# sdram.net
KiCad netlist of a schematic drawn in Altium Designer
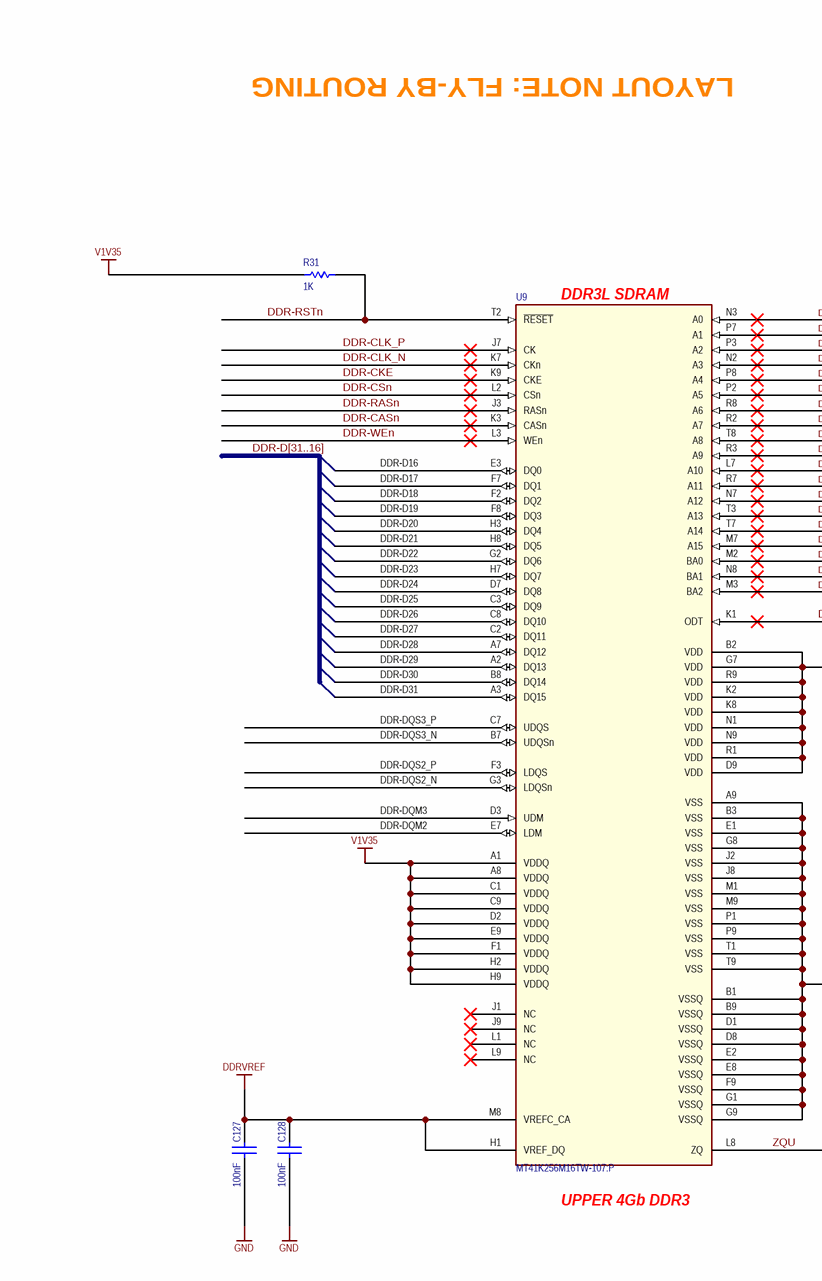
[diagram p0: sdram.SchDoc, top left]
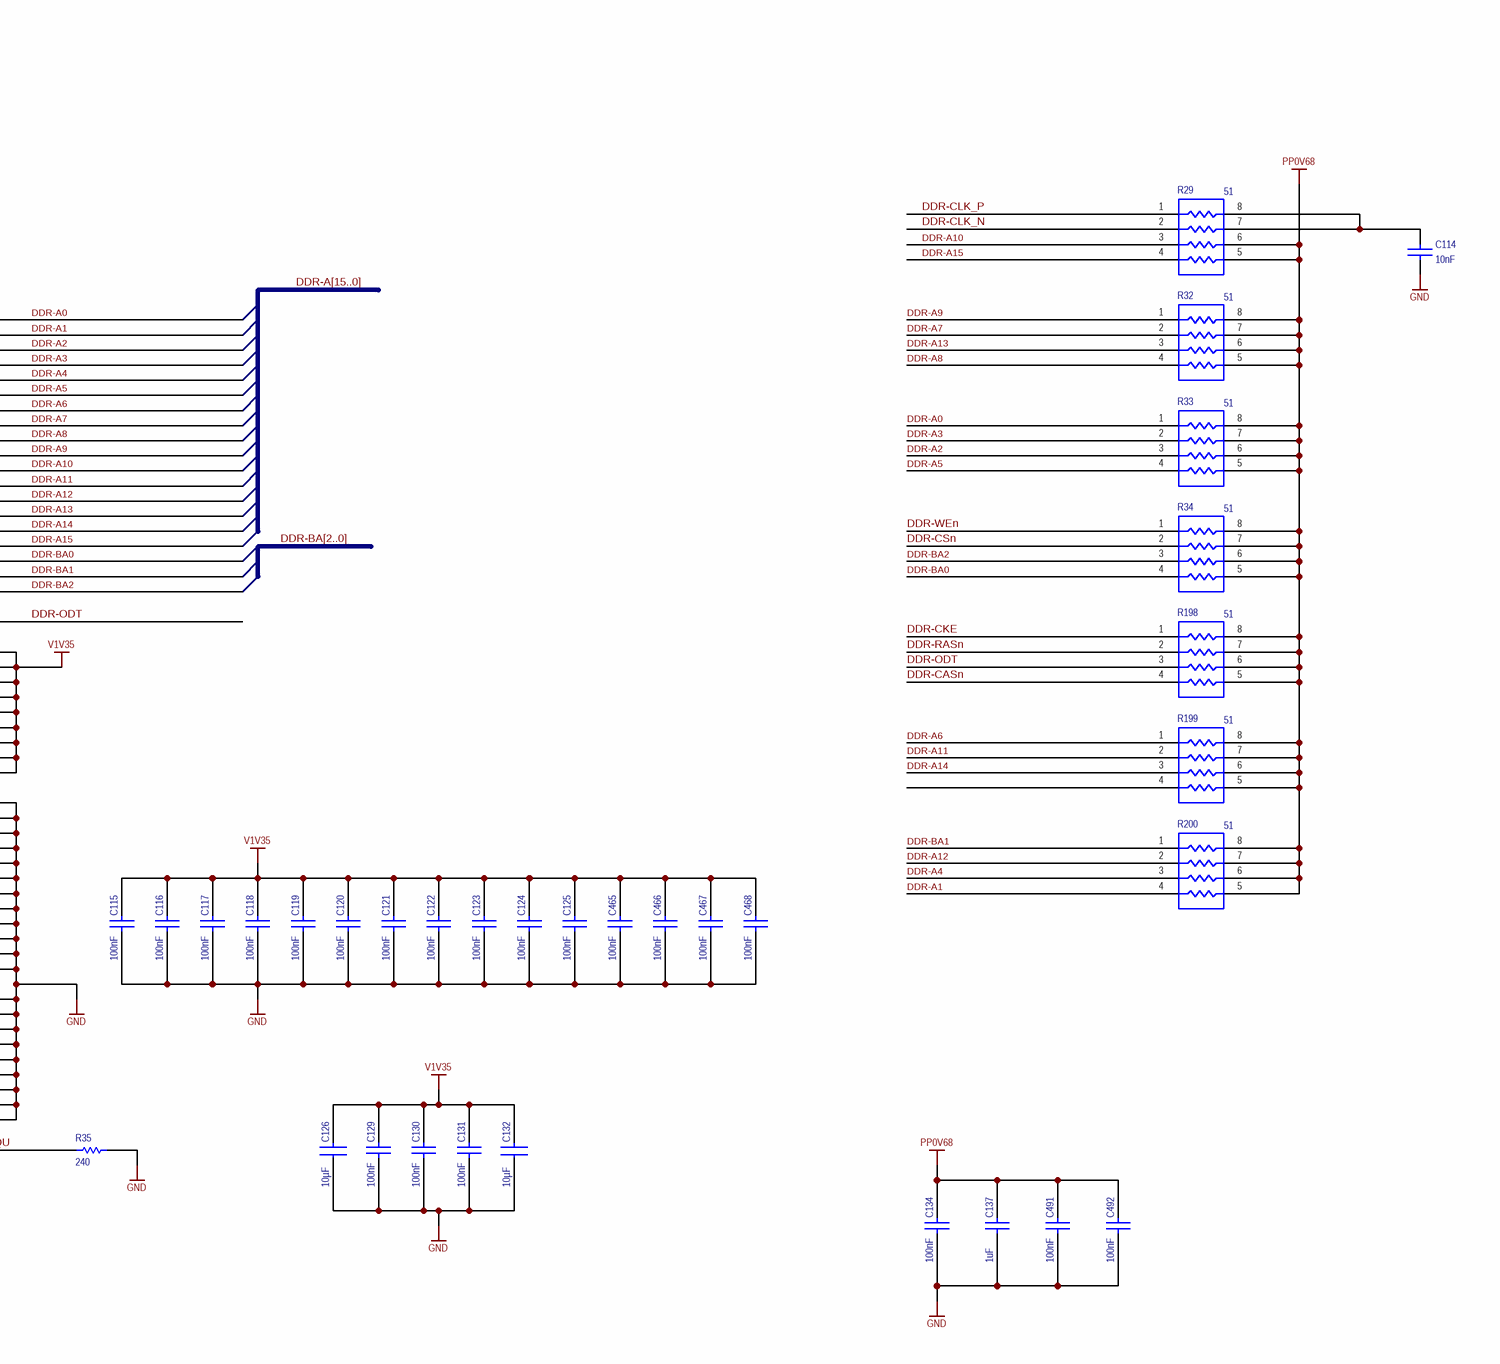
[diagram p1: sdram.SchDoc, top right]
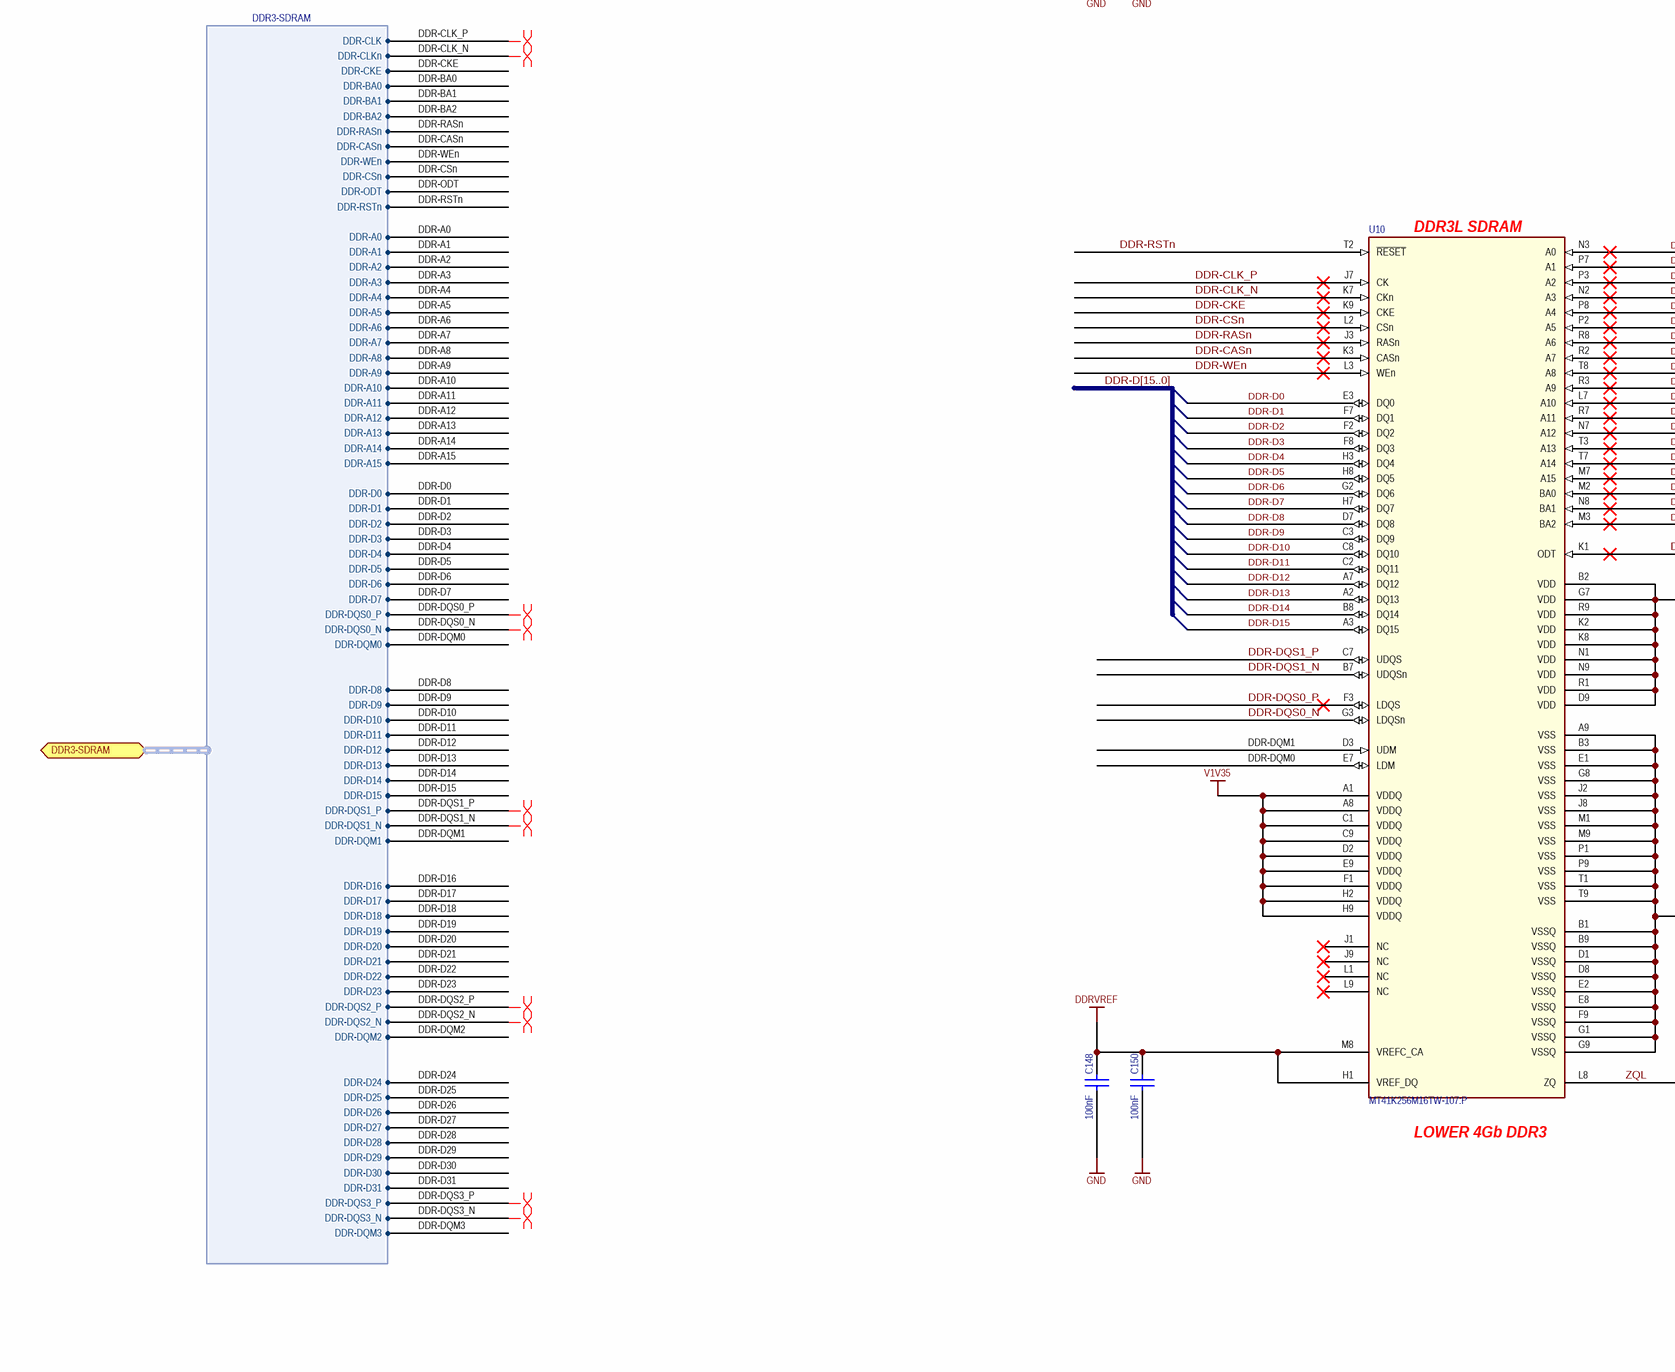
[diagram p2: sdram.SchDoc, bottom left]
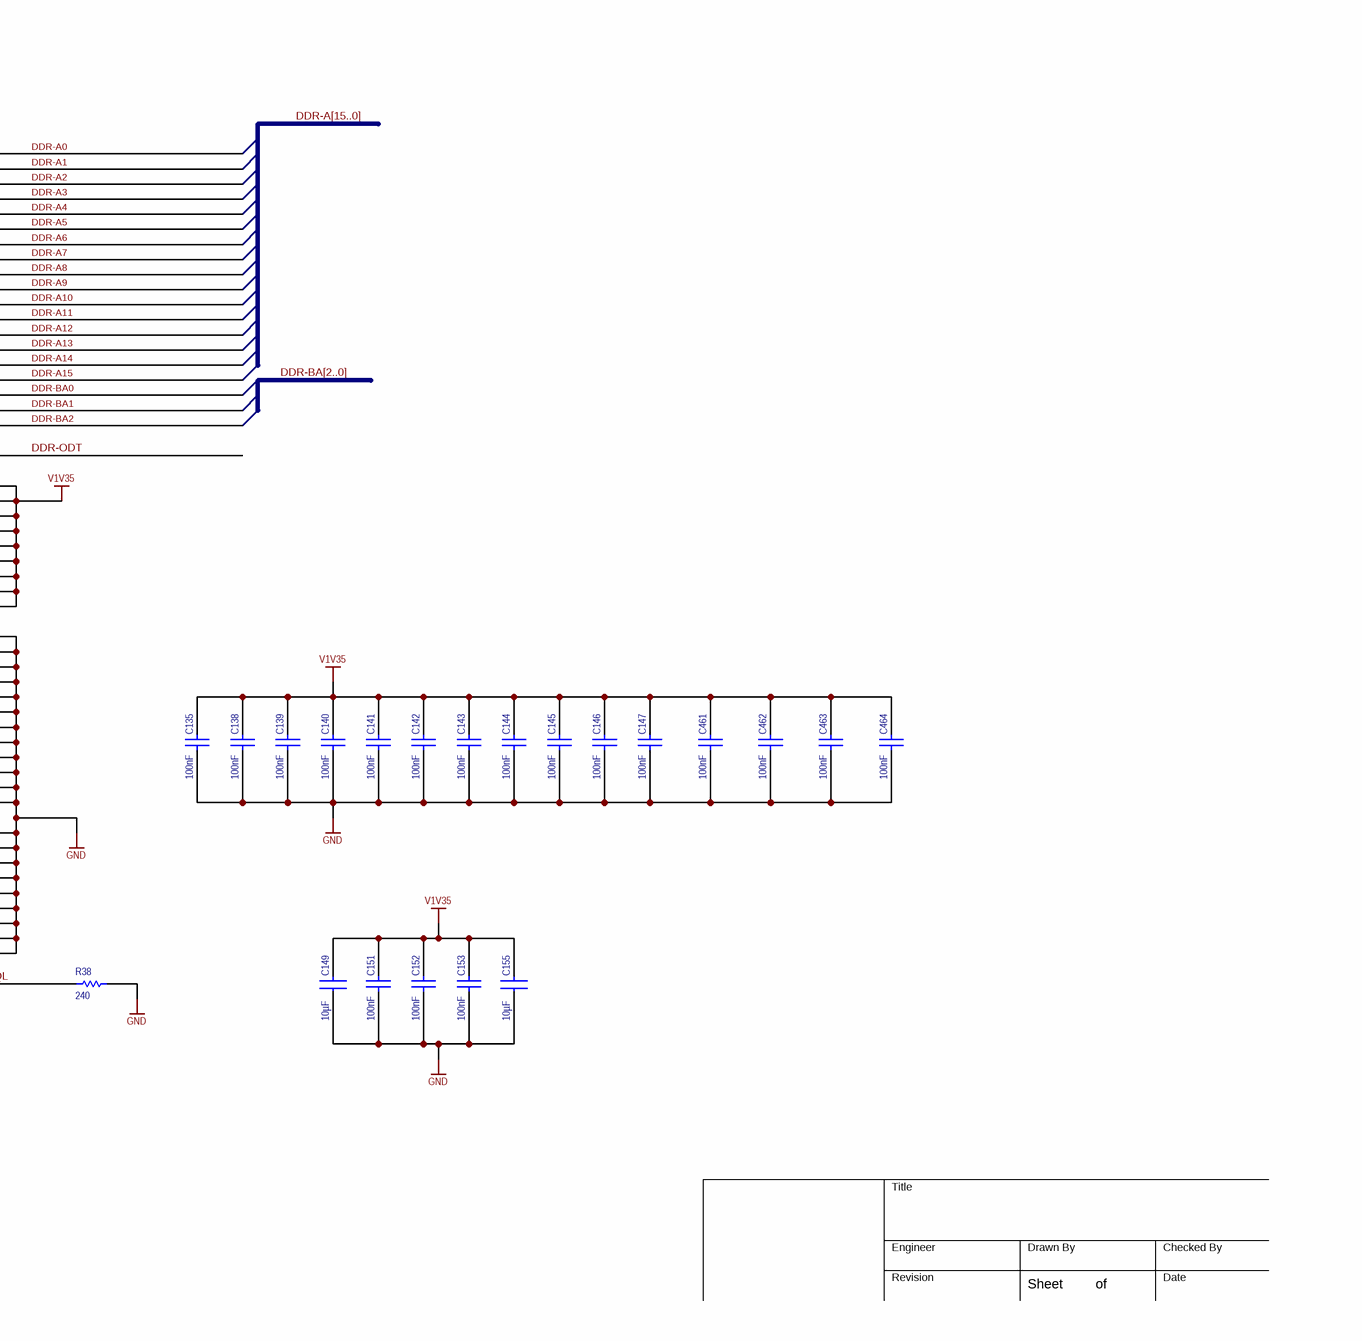
[diagram p3: sdram.SchDoc, bottom right]

(export (version "E")
  (design (tool "Eeschema 10.0.6"))
  (components
    (comp (ref "C114")
      (value "10nF")
      (footprint "generic:0402")
      (description "Ceramic Capacitor 10nF ±10% 25V X7R 0402")
      (fields (field (name "VOLTAGE") "25V") (field (name "MANUFACTURER") "Murata"))
      (libsource (lib "Graviton") (part "CAP 0402"))
    )
    (comp (ref "C115")
      (value "100nF")
      (footprint "generic:CAPC1005X56N")
      (description "Ceramic Capacitor 100nF ±10% 16V X7R 0402")
      (fields (field (name "MANUFACTURER") "Murata") (field (name "TOLERANCE") "±10%"))
      (libsource (lib "murata") (part "GRM155R71A104KA01J"))
    )
    (comp (ref "C116")
      (value "100nF")
      (footprint "generic:CAPC1005X56N")
      (description "Ceramic Capacitor 100nF ±10% 16V X7R 0402")
      (fields (field (name "MANUFACTURER") "Murata") (field (name "TOLERANCE") "±10%"))
      (libsource (lib "murata") (part "GRM155R71A104KA01J"))
    )
    (comp (ref "C117")
      (value "100nF")
      (footprint "generic:CAPC1005X56N")
      (description "Ceramic Capacitor 100nF ±10% 16V X7R 0402")
      (fields (field (name "MANUFACTURER") "Murata") (field (name "TOLERANCE") "±10%"))
      (libsource (lib "murata") (part "GRM155R71A104KA01J"))
    )
    (comp (ref "C118")
      (value "100nF")
      (footprint "generic:CAPC1005X56N")
      (description "Ceramic Capacitor 100nF ±10% 16V X7R 0402")
      (fields (field (name "MANUFACTURER") "Murata") (field (name "TOLERANCE") "±10%"))
      (libsource (lib "murata") (part "GRM155R71A104KA01J"))
    )
    (comp (ref "C119")
      (value "100nF")
      (footprint "generic:CAPC1005X56N")
      (description "Ceramic Capacitor 100nF ±10% 16V X7R 0402")
      (fields (field (name "MANUFACTURER") "Murata") (field (name "TOLERANCE") "±10%"))
      (libsource (lib "murata") (part "GRM155R71A104KA01J"))
    )
    (comp (ref "C120")
      (value "100nF")
      (footprint "generic:CAPC1005X56N")
      (description "Ceramic Capacitor 100nF ±10% 16V X7R 0402")
      (fields (field (name "MANUFACTURER") "Murata") (field (name "TOLERANCE") "±10%"))
      (libsource (lib "murata") (part "GRM155R71A104KA01J"))
    )
    (comp (ref "C121")
      (value "100nF")
      (footprint "generic:CAPC1005X56N")
      (description "Ceramic Capacitor 100nF ±10% 16V X7R 0402")
      (fields (field (name "MANUFACTURER") "Murata") (field (name "TOLERANCE") "±10%"))
      (libsource (lib "murata") (part "GRM155R71A104KA01J"))
    )
    (comp (ref "C122")
      (value "100nF")
      (footprint "generic:CAPC1005X56N")
      (description "Ceramic Capacitor 100nF ±10% 16V X7R 0402")
      (fields (field (name "MANUFACTURER") "Murata") (field (name "TOLERANCE") "±10%"))
      (libsource (lib "murata") (part "GRM155R71A104KA01J"))
    )
    (comp (ref "C123")
      (value "100nF")
      (footprint "generic:CAPC1005X56N")
      (description "Ceramic Capacitor 100nF ±10% 16V X7R 0402")
      (fields (field (name "MANUFACTURER") "Murata") (field (name "TOLERANCE") "±10%"))
      (libsource (lib "murata") (part "GRM155R71A104KA01J"))
    )
    (comp (ref "C124")
      (value "100nF")
      (footprint "generic:CAPC1005X56N")
      (description "Ceramic Capacitor 100nF ±10% 16V X7R 0402")
      (fields (field (name "MANUFACTURER") "Murata") (field (name "TOLERANCE") "±10%"))
      (libsource (lib "murata") (part "GRM155R71A104KA01J"))
    )
    (comp (ref "C125")
      (value "100nF")
      (footprint "generic:CAPC1005X56N")
      (description "Ceramic Capacitor 100nF ±10% 16V X7R 0402")
      (fields (field (name "MANUFACTURER") "Murata") (field (name "TOLERANCE") "±10%"))
      (libsource (lib "murata") (part "GRM155R71A104KA01J"))
    )
    (comp (ref "C126")
      (value "10µF")
      (footprint "0603")
      (description "Ceramic Capacitor 10uF ±20% 25V X5R 0603")
      (fields (field (name "MANUFACTURER") "Samsung") (field (name "TOLERANCE") "±20%"))
      (libsource (lib "BEAGLEBONEBLACK_REV A5B") (part "CAP_4.7uF_X5R_6.3V_10%_0603"))
    )
    (comp (ref "C127")
      (value "100nF")
      (footprint "generic:CAPC1005X56N")
      (description "Ceramic Capacitor 100nF ±10% 16V X7R 0402")
      (fields (field (name "MANUFACTURER") "Murata") (field (name "TOLERANCE") "±10%"))
      (libsource (lib "murata") (part "GRM155R71A104KA01J"))
    )
    (comp (ref "C128")
      (value "100nF")
      (footprint "generic:CAPC1005X56N")
      (description "Ceramic Capacitor 100nF ±10% 16V X7R 0402")
      (fields (field (name "MANUFACTURER") "Murata") (field (name "TOLERANCE") "±10%"))
      (libsource (lib "murata") (part "GRM155R71A104KA01J"))
    )
    (comp (ref "C129")
      (value "100nF")
      (footprint "generic:CAPC1005X56N")
      (description "Ceramic Capacitor 100nF ±10% 16V X7R 0402")
      (fields (field (name "MANUFACTURER") "Murata") (field (name "TOLERANCE") "±10%"))
      (libsource (lib "murata") (part "GRM155R71A104KA01J"))
    )
    (comp (ref "C130")
      (value "100nF")
      (footprint "generic:CAPC1005X56N")
      (description "Ceramic Capacitor 100nF ±10% 16V X7R 0402")
      (fields (field (name "MANUFACTURER") "Murata") (field (name "TOLERANCE") "±10%"))
      (libsource (lib "murata") (part "GRM155R71A104KA01J"))
    )
    (comp (ref "C131")
      (value "100nF")
      (footprint "generic:CAPC1005X56N")
      (description "Ceramic Capacitor 100nF ±10% 16V X7R 0402")
      (fields (field (name "MANUFACTURER") "Murata") (field (name "TOLERANCE") "±10%"))
      (libsource (lib "murata") (part "GRM155R71A104KA01J"))
    )
    (comp (ref "C132")
      (value "10µF")
      (footprint "0603")
      (description "Ceramic Capacitor 10uF ±20% 25V X5R 0603")
      (fields (field (name "MANUFACTURER") "Samsung") (field (name "TOLERANCE") "±20%"))
      (libsource (lib "BEAGLEBONEBLACK_REV A5B") (part "CAP_4.7uF_X5R_6.3V_10%_0603"))
    )
    (comp (ref "C134")
      (value "100nF")
      (footprint "generic:CAPC1005X56N")
      (description "Ceramic Capacitor 100nF ±10% 16V X7R 0402")
      (fields (field (name "MANUFACTURER") "Murata") (field (name "TOLERANCE") "±10%"))
      (libsource (lib "murata") (part "GRM155R71A104KA01J"))
    )
    (comp (ref "C135")
      (value "100nF")
      (footprint "generic:CAPC1005X56N")
      (description "Ceramic Capacitor 100nF ±10% 16V X7R 0402")
      (fields (field (name "MANUFACTURER") "Murata") (field (name "TOLERANCE") "±10%"))
      (libsource (lib "murata") (part "GRM155R71A104KA01J"))
    )
    (comp (ref "C137")
      (value "1uF")
      (footprint "generic:CAPC1005X56N")
      (description "Ceramic Capacitor 1uF ±10% 10V X5R 0402")
      (fields (field (name "VOLTAGE") "10V") (field (name "MANUFACTURER") "Murata"))
      (libsource (lib "Graviton") (part "CAP 0402"))
    )
    (comp (ref "C138")
      (value "100nF")
      (footprint "generic:CAPC1005X56N")
      (description "Ceramic Capacitor 100nF ±10% 16V X7R 0402")
      (fields (field (name "MANUFACTURER") "Murata") (field (name "TOLERANCE") "±10%"))
      (libsource (lib "murata") (part "GRM155R71A104KA01J"))
    )
    (comp (ref "C139")
      (value "100nF")
      (footprint "generic:CAPC1005X56N")
      (description "Ceramic Capacitor 100nF ±10% 16V X7R 0402")
      (fields (field (name "MANUFACTURER") "Murata") (field (name "TOLERANCE") "±10%"))
      (libsource (lib "murata") (part "GRM155R71A104KA01J"))
    )
    (comp (ref "C140")
      (value "100nF")
      (footprint "generic:CAPC1005X56N")
      (description "Ceramic Capacitor 100nF ±10% 16V X7R 0402")
      (fields (field (name "MANUFACTURER") "Murata") (field (name "TOLERANCE") "±10%"))
      (libsource (lib "murata") (part "GRM155R71A104KA01J"))
    )
    (comp (ref "C141")
      (value "100nF")
      (footprint "generic:CAPC1005X56N")
      (description "Ceramic Capacitor 100nF ±10% 16V X7R 0402")
      (fields (field (name "MANUFACTURER") "Murata") (field (name "TOLERANCE") "±10%"))
      (libsource (lib "murata") (part "GRM155R71A104KA01J"))
    )
    (comp (ref "C142")
      (value "100nF")
      (footprint "generic:CAPC1005X56N")
      (description "Ceramic Capacitor 100nF ±10% 16V X7R 0402")
      (fields (field (name "MANUFACTURER") "Murata") (field (name "TOLERANCE") "±10%"))
      (libsource (lib "murata") (part "GRM155R71A104KA01J"))
    )
    (comp (ref "C143")
      (value "100nF")
      (footprint "generic:CAPC1005X56N")
      (description "Ceramic Capacitor 100nF ±10% 16V X7R 0402")
      (fields (field (name "MANUFACTURER") "Murata") (field (name "TOLERANCE") "±10%"))
      (libsource (lib "murata") (part "GRM155R71A104KA01J"))
    )
    (comp (ref "C144")
      (value "100nF")
      (footprint "generic:CAPC1005X56N")
      (description "Ceramic Capacitor 100nF ±10% 16V X7R 0402")
      (fields (field (name "MANUFACTURER") "Murata") (field (name "TOLERANCE") "±10%"))
      (libsource (lib "murata") (part "GRM155R71A104KA01J"))
    )
    (comp (ref "C145")
      (value "100nF")
      (footprint "generic:CAPC1005X56N")
      (description "Ceramic Capacitor 100nF ±10% 16V X7R 0402")
      (fields (field (name "MANUFACTURER") "Murata") (field (name "TOLERANCE") "±10%"))
      (libsource (lib "murata") (part "GRM155R71A104KA01J"))
    )
    (comp (ref "C146")
      (value "100nF")
      (footprint "generic:CAPC1005X56N")
      (description "Ceramic Capacitor 100nF ±10% 16V X7R 0402")
      (fields (field (name "MANUFACTURER") "Murata") (field (name "TOLERANCE") "±10%"))
      (libsource (lib "murata") (part "GRM155R71A104KA01J"))
    )
    (comp (ref "C147")
      (value "100nF")
      (footprint "generic:CAPC1005X56N")
      (description "Ceramic Capacitor 100nF ±10% 16V X7R 0402")
      (fields (field (name "MANUFACTURER") "Murata") (field (name "TOLERANCE") "±10%"))
      (libsource (lib "murata") (part "GRM155R71A104KA01J"))
    )
    (comp (ref "C148")
      (value "100nF")
      (footprint "generic:CAPC1005X56N")
      (description "Ceramic Capacitor 100nF ±10% 16V X7R 0402")
      (fields (field (name "MANUFACTURER") "Murata") (field (name "TOLERANCE") "±10%"))
      (libsource (lib "murata") (part "GRM155R71A104KA01J"))
    )
    (comp (ref "C149")
      (value "10µF")
      (footprint "0603")
      (description "Ceramic Capacitor 10uF ±20% 25V X5R 0603")
      (fields (field (name "MANUFACTURER") "Samsung") (field (name "TOLERANCE") "±20%"))
      (libsource (lib "BEAGLEBONEBLACK_REV A5B") (part "CAP_4.7uF_X5R_6.3V_10%_0603"))
    )
    (comp (ref "C150")
      (value "100nF")
      (footprint "generic:CAPC1005X56N")
      (description "Ceramic Capacitor 100nF ±10% 16V X7R 0402")
      (fields (field (name "MANUFACTURER") "Murata") (field (name "TOLERANCE") "±10%"))
      (libsource (lib "murata") (part "GRM155R71A104KA01J"))
    )
    (comp (ref "C151")
      (value "100nF")
      (footprint "generic:CAPC1005X56N")
      (description "Ceramic Capacitor 100nF ±10% 16V X7R 0402")
      (fields (field (name "MANUFACTURER") "Murata") (field (name "TOLERANCE") "±10%"))
      (libsource (lib "murata") (part "GRM155R71A104KA01J"))
    )
    (comp (ref "C152")
      (value "100nF")
      (footprint "generic:CAPC1005X56N")
      (description "Ceramic Capacitor 100nF ±10% 16V X7R 0402")
      (fields (field (name "MANUFACTURER") "Murata") (field (name "TOLERANCE") "±10%"))
      (libsource (lib "murata") (part "GRM155R71A104KA01J"))
    )
    (comp (ref "C153")
      (value "100nF")
      (footprint "generic:CAPC1005X56N")
      (description "Ceramic Capacitor 100nF ±10% 16V X7R 0402")
      (fields (field (name "MANUFACTURER") "Murata") (field (name "TOLERANCE") "±10%"))
      (libsource (lib "murata") (part "GRM155R71A104KA01J"))
    )
    (comp (ref "C155")
      (value "10µF")
      (footprint "0603")
      (description "Ceramic Capacitor 10uF ±20% 25V X5R 0603")
      (fields (field (name "MANUFACTURER") "Samsung") (field (name "TOLERANCE") "±20%"))
      (libsource (lib "BEAGLEBONEBLACK_REV A5B") (part "CAP_4.7uF_X5R_6.3V_10%_0603"))
    )
    (comp (ref "C461")
      (value "100nF")
      (footprint "generic:CAPC1005X56N")
      (description "Ceramic Capacitor 100nF ±10% 16V X7R 0402")
      (fields (field (name "MANUFACTURER") "Murata") (field (name "TOLERANCE") "±10%"))
      (libsource (lib "murata") (part "GRM155R71A104KA01J"))
    )
    (comp (ref "C462")
      (value "100nF")
      (footprint "generic:CAPC1005X56N")
      (description "Ceramic Capacitor 100nF ±10% 16V X7R 0402")
      (fields (field (name "MANUFACTURER") "Murata") (field (name "TOLERANCE") "±10%"))
      (libsource (lib "murata") (part "GRM155R71A104KA01J"))
    )
    (comp (ref "C463")
      (value "100nF")
      (footprint "generic:CAPC1005X56N")
      (description "Ceramic Capacitor 100nF ±10% 16V X7R 0402")
      (fields (field (name "MANUFACTURER") "Murata") (field (name "TOLERANCE") "±10%"))
      (libsource (lib "murata") (part "GRM155R71A104KA01J"))
    )
    (comp (ref "C464")
      (value "100nF")
      (footprint "generic:CAPC1005X56N")
      (description "Ceramic Capacitor 100nF ±10% 16V X7R 0402")
      (fields (field (name "MANUFACTURER") "Murata") (field (name "TOLERANCE") "±10%"))
      (libsource (lib "murata") (part "GRM155R71A104KA01J"))
    )
    (comp (ref "C465")
      (value "100nF")
      (footprint "generic:CAPC1005X56N")
      (description "Ceramic Capacitor 100nF ±10% 16V X7R 0402")
      (fields (field (name "MANUFACTURER") "Murata") (field (name "TOLERANCE") "±10%"))
      (libsource (lib "murata") (part "GRM155R71A104KA01J"))
    )
    (comp (ref "C466")
      (value "100nF")
      (footprint "generic:CAPC1005X56N")
      (description "Ceramic Capacitor 100nF ±10% 16V X7R 0402")
      (fields (field (name "MANUFACTURER") "Murata") (field (name "TOLERANCE") "±10%"))
      (libsource (lib "murata") (part "GRM155R71A104KA01J"))
    )
    (comp (ref "C467")
      (value "100nF")
      (footprint "generic:CAPC1005X56N")
      (description "Ceramic Capacitor 100nF ±10% 16V X7R 0402")
      (fields (field (name "MANUFACTURER") "Murata") (field (name "TOLERANCE") "±10%"))
      (libsource (lib "murata") (part "GRM155R71A104KA01J"))
    )
    (comp (ref "C468")
      (value "100nF")
      (footprint "generic:CAPC1005X56N")
      (description "Ceramic Capacitor 100nF ±10% 16V X7R 0402")
      (fields (field (name "MANUFACTURER") "Murata") (field (name "TOLERANCE") "±10%"))
      (libsource (lib "murata") (part "GRM155R71A104KA01J"))
    )
    (comp (ref "C491")
      (value "100nF")
      (footprint "generic:CAPC1005X56N")
      (description "Ceramic Capacitor 100nF ±10% 16V X7R 0402")
      (fields (field (name "MANUFACTURER") "Murata") (field (name "TOLERANCE") "±10%"))
      (libsource (lib "murata") (part "GRM155R71A104KA01J"))
    )
    (comp (ref "C492")
      (value "100nF")
      (footprint "generic:CAPC1005X56N")
      (description "Ceramic Capacitor 100nF ±10% 16V X7R 0402")
      (fields (field (name "MANUFACTURER") "Murata") (field (name "TOLERANCE") "±10%"))
      (libsource (lib "murata") (part "GRM155R71A104KA01J"))
    )
    (comp (ref "R29")
      (value "51")
      (footprint "generic:0804-PAK-8")
      (description "4 Resistor Array 51 ±5% 0804")
      (fields (field (name "MANUFACTURER") "CTS") (field (name "TOLERANCE") "±5%"))
      (libsource (lib "generic") (part "RESPAK x4 0804"))
    )
    (comp (ref "R31")
      (value "1K")
      (footprint "generic:0402")
      (description "Thick Film Resistor 1k ±1% 0402")
      (fields (field (name "MANUFACTURER") "Yageo") (field (name "TOLERANCE") "±1%"))
      (libsource (lib "generic") (part "RES 0402"))
    )
    (comp (ref "R32")
      (value "51")
      (footprint "generic:0804-PAK-8")
      (description "4 Resistor Array 51 ±5% 0804")
      (fields (field (name "MANUFACTURER") "CTS") (field (name "TOLERANCE") "±5%"))
      (libsource (lib "generic") (part "RESPAK x4 0804"))
    )
    (comp (ref "R33")
      (value "51")
      (footprint "generic:0804-PAK-8")
      (description "4 Resistor Array 51 ±5% 0804")
      (fields (field (name "MANUFACTURER") "CTS") (field (name "TOLERANCE") "±5%"))
      (libsource (lib "generic") (part "RESPAK x4 0804"))
    )
    (comp (ref "R34")
      (value "51")
      (footprint "generic:0804-PAK-8")
      (description "4 Resistor Array 51 ±5% 0804")
      (fields (field (name "MANUFACTURER") "CTS") (field (name "TOLERANCE") "±5%"))
      (libsource (lib "generic") (part "RESPAK x4 0804"))
    )
    (comp (ref "R35")
      (value "240")
      (footprint "generic:0402")
      (description "Thick Film Resistor 240 ±1% 0402")
      (fields (field (name "MANUFACTURER") "Panasonic") (field (name "TOLERANCE") "±1%"))
      (libsource (lib "generic") (part "RES 0402"))
    )
    (comp (ref "R38")
      (value "240")
      (footprint "generic:0402")
      (description "Thick Film Resistor 240 ±1% 0402")
      (fields (field (name "MANUFACTURER") "Panasonic") (field (name "TOLERANCE") "±1%"))
      (libsource (lib "generic") (part "RES 0402"))
    )
    (comp (ref "R198")
      (value "51")
      (footprint "generic:0804-PAK-8")
      (description "4 Resistor Array 51 ±5% 0804")
      (fields (field (name "MANUFACTURER") "CTS") (field (name "TOLERANCE") "±5%"))
      (libsource (lib "generic") (part "RESPAK x4 0804"))
    )
    (comp (ref "R199")
      (value "51")
      (footprint "generic:0804-PAK-8")
      (description "4 Resistor Array 51 ±5% 0804")
      (fields (field (name "MANUFACTURER") "CTS") (field (name "TOLERANCE") "±5%"))
      (libsource (lib "generic") (part "RESPAK x4 0804"))
    )
    (comp (ref "R200")
      (value "51")
      (footprint "generic:0804-PAK-8")
      (description "4 Resistor Array 51 ±5% 0804")
      (fields (field (name "MANUFACTURER") "CTS") (field (name "TOLERANCE") "±5%"))
      (libsource (lib "generic") (part "RESPAK x4 0804"))
    )
    (comp (ref "U9")
      (value "MT41K256M16TW-107:P")
      (footprint "BGA96_T9_P8_9X14")
      (description "DDR2 SDRAM 2Gb (256Mx8)")
      (fields (field (name "MANUFACTURER") "Micron Technology"))
      (libsource (lib "BEAGLEBONEBLACK_REV A5B") (part "MT41K256M16HA"))
    )
    (comp (ref "U10")
      (value "MT41K256M16TW-107:P")
      (footprint "BGA96_T9_P8_9X14")
      (description "DDR2 SDRAM 2Gb (256Mx8)")
      (fields (field (name "MANUFACTURER") "Micron Technology"))
      (libsource (lib "BEAGLEBONEBLACK_REV A5B") (part "MT41K256M16HA"))
    )
  )
  (nets
    (net (code "2") (name "/DDR-A0") (class "Default")
      (node (ref "R33") (pin "1") (pinfunction "1_1") (pintype "passive"))
      (node (ref "U10") (pin "N3") (pinfunction "A0_N3") (pintype "input"))
      (node (ref "U9") (pin "N3") (pinfunction "A0_N3") (pintype "input"))
    )
    (net (code "3") (name "/DDR-A1") (class "Default")
      (node (ref "R200") (pin "4") (pinfunction "4_4") (pintype "passive"))
      (node (ref "U10") (pin "P7") (pinfunction "A1_P7") (pintype "input"))
      (node (ref "U9") (pin "P7") (pinfunction "A1_P7") (pintype "input"))
    )
    (net (code "4") (name "/DDR-A2") (class "Default")
      (node (ref "R33") (pin "3") (pinfunction "3_3") (pintype "passive"))
      (node (ref "U10") (pin "P3") (pinfunction "A2_P3") (pintype "input"))
      (node (ref "U9") (pin "P3") (pinfunction "A2_P3") (pintype "input"))
    )
    (net (code "5") (name "/DDR-A3") (class "Default")
      (node (ref "R33") (pin "2") (pinfunction "2_2") (pintype "passive"))
      (node (ref "U10") (pin "N2") (pinfunction "A3_N2") (pintype "input"))
      (node (ref "U9") (pin "N2") (pinfunction "A3_N2") (pintype "input"))
    )
    (net (code "6") (name "/DDR-A4") (class "Default")
      (node (ref "R200") (pin "3") (pinfunction "3_3") (pintype "passive"))
      (node (ref "U10") (pin "P8") (pinfunction "A4_P8") (pintype "input"))
      (node (ref "U9") (pin "P8") (pinfunction "A4_P8") (pintype "input"))
    )
    (net (code "7") (name "/DDR-A5") (class "Default")
      (node (ref "R33") (pin "4") (pinfunction "4_4") (pintype "passive"))
      (node (ref "U10") (pin "P2") (pinfunction "A5_P2") (pintype "input"))
      (node (ref "U9") (pin "P2") (pinfunction "A5_P2") (pintype "input"))
    )
    (net (code "8") (name "/DDR-A6") (class "Default")
      (node (ref "R199") (pin "1") (pinfunction "1_1") (pintype "passive"))
      (node (ref "U10") (pin "R8") (pinfunction "A6_R8") (pintype "input"))
      (node (ref "U9") (pin "R8") (pinfunction "A6_R8") (pintype "input"))
    )
    (net (code "9") (name "/DDR-A7") (class "Default")
      (node (ref "R32") (pin "2") (pinfunction "2_2") (pintype "passive"))
      (node (ref "U10") (pin "R2") (pinfunction "A7_R2") (pintype "input"))
      (node (ref "U9") (pin "R2") (pinfunction "A7_R2") (pintype "input"))
    )
    (net (code "10") (name "/DDR-A8") (class "Default")
      (node (ref "R32") (pin "4") (pinfunction "4_4") (pintype "passive"))
      (node (ref "U10") (pin "T8") (pinfunction "A8_T8") (pintype "input"))
      (node (ref "U9") (pin "T8") (pinfunction "A8_T8") (pintype "input"))
    )
    (net (code "11") (name "/DDR-A9") (class "Default")
      (node (ref "R32") (pin "1") (pinfunction "1_1") (pintype "passive"))
      (node (ref "U10") (pin "R3") (pinfunction "A9_R3") (pintype "input"))
      (node (ref "U9") (pin "R3") (pinfunction "A9_R3") (pintype "input"))
    )
    (net (code "12") (name "/DDR-A10") (class "Default")
      (node (ref "R29") (pin "3") (pinfunction "3_3") (pintype "passive"))
      (node (ref "U10") (pin "L7") (pinfunction "A10_L7") (pintype "input"))
      (node (ref "U9") (pin "L7") (pinfunction "A10_L7") (pintype "input"))
    )
    (net (code "13") (name "/DDR-A11") (class "Default")
      (node (ref "R199") (pin "2") (pinfunction "2_2") (pintype "passive"))
      (node (ref "U10") (pin "R7") (pinfunction "A11_R7") (pintype "input"))
      (node (ref "U9") (pin "R7") (pinfunction "A11_R7") (pintype "input"))
    )
    (net (code "14") (name "/DDR-A12") (class "Default")
      (node (ref "R200") (pin "2") (pinfunction "2_2") (pintype "passive"))
      (node (ref "U10") (pin "N7") (pinfunction "A12_N7") (pintype "input"))
      (node (ref "U9") (pin "N7") (pinfunction "A12_N7") (pintype "input"))
    )
    (net (code "15") (name "/DDR-A13") (class "Default")
      (node (ref "R32") (pin "3") (pinfunction "3_3") (pintype "passive"))
      (node (ref "U10") (pin "T3") (pinfunction "A13_T3") (pintype "input"))
      (node (ref "U9") (pin "T3") (pinfunction "A13_T3") (pintype "input"))
    )
    (net (code "16") (name "/DDR-A14") (class "Default")
      (node (ref "R199") (pin "3") (pinfunction "3_3") (pintype "passive"))
      (node (ref "U10") (pin "T7") (pinfunction "A14_T7") (pintype "input"))
      (node (ref "U9") (pin "T7") (pinfunction "A14_T7") (pintype "input"))
    )
    (net (code "17") (name "/DDR-A15") (class "Default")
      (node (ref "R29") (pin "4") (pinfunction "4_4") (pintype "passive"))
      (node (ref "U10") (pin "M7") (pinfunction "A15_M7") (pintype "input"))
      (node (ref "U9") (pin "M7") (pinfunction "A15_M7") (pintype "input"))
    )
    (net (code "19") (name "/DDR-BA0") (class "Default")
      (node (ref "R34") (pin "4") (pinfunction "4_4") (pintype "passive"))
      (node (ref "U10") (pin "M2") (pinfunction "BA0_M2") (pintype "input"))
      (node (ref "U9") (pin "M2") (pinfunction "BA0_M2") (pintype "input"))
    )
    (net (code "20") (name "/DDR-BA1") (class "Default")
      (node (ref "R200") (pin "1") (pinfunction "1_1") (pintype "passive"))
      (node (ref "U10") (pin "N8") (pinfunction "BA1_N8") (pintype "input"))
      (node (ref "U9") (pin "N8") (pinfunction "BA1_N8") (pintype "input"))
    )
    (net (code "21") (name "/DDR-BA2") (class "Default")
      (node (ref "R34") (pin "3") (pinfunction "3_3") (pintype "passive"))
      (node (ref "U10") (pin "M3") (pinfunction "BA2_M3") (pintype "input"))
      (node (ref "U9") (pin "M3") (pinfunction "BA2_M3") (pintype "input"))
    )
    (net (code "23") (name "/DDR-CASn") (class "Default")
      (node (ref "R198") (pin "4") (pinfunction "4_4") (pintype "passive"))
      (node (ref "U10") (pin "K3") (pinfunction "CASn_K3") (pintype "input"))
      (node (ref "U9") (pin "K3") (pinfunction "CASn_K3") (pintype "input"))
    )
    (net (code "24") (name "/DDR-CKE") (class "Default")
      (node (ref "R198") (pin "1") (pinfunction "1_1") (pintype "passive"))
      (node (ref "U10") (pin "K9") (pinfunction "CKE_K9") (pintype "input"))
      (node (ref "U9") (pin "K9") (pinfunction "CKE_K9") (pintype "input"))
    )
    (net (code "25") (name "/DDR-CLK_N") (class "Default")
      (node (ref "R29") (pin "2") (pinfunction "2_2") (pintype "passive"))
      (node (ref "U10") (pin "K7") (pinfunction "CKn_K7") (pintype "input"))
      (node (ref "U9") (pin "K7") (pinfunction "CKn_K7") (pintype "input"))
    )
    (net (code "26") (name "/DDR-CLK_P") (class "Default")
      (node (ref "R29") (pin "1") (pinfunction "1_1") (pintype "passive"))
      (node (ref "U10") (pin "J7") (pinfunction "CK_J7") (pintype "input"))
      (node (ref "U9") (pin "J7") (pinfunction "CK_J7") (pintype "input"))
    )
    (net (code "27") (name "/DDR-CSn") (class "Default")
      (node (ref "R34") (pin "2") (pinfunction "2_2") (pintype "passive"))
      (node (ref "U10") (pin "L2") (pinfunction "CSn_L2") (pintype "input"))
      (node (ref "U9") (pin "L2") (pinfunction "CSn_L2") (pintype "input"))
    )
    (net (code "28") (name "/DDR-D0") (class "Default")
      (node (ref "U10") (pin "E3") (pinfunction "DQ0_E3") (pintype "bidirectional"))
    )
    (net (code "29") (name "/DDR-D1") (class "Default")
      (node (ref "U10") (pin "F7") (pinfunction "DQ1_F7") (pintype "bidirectional"))
    )
    (net (code "30") (name "/DDR-D2") (class "Default")
      (node (ref "U10") (pin "F2") (pinfunction "DQ2_F2") (pintype "bidirectional"))
    )
    (net (code "31") (name "/DDR-D3") (class "Default")
      (node (ref "U10") (pin "F8") (pinfunction "DQ3_F8") (pintype "bidirectional"))
    )
    (net (code "32") (name "/DDR-D4") (class "Default")
      (node (ref "U10") (pin "H3") (pinfunction "DQ4_H3") (pintype "bidirectional"))
    )
    (net (code "33") (name "/DDR-D5") (class "Default")
      (node (ref "U10") (pin "H8") (pinfunction "DQ5_H8") (pintype "bidirectional"))
    )
    (net (code "34") (name "/DDR-D6") (class "Default")
      (node (ref "U10") (pin "G2") (pinfunction "DQ6_G2") (pintype "bidirectional"))
    )
    (net (code "35") (name "/DDR-D7") (class "Default")
      (node (ref "U10") (pin "H7") (pinfunction "DQ7_H7") (pintype "bidirectional"))
    )
    (net (code "36") (name "/DDR-D8") (class "Default")
      (node (ref "U10") (pin "D7") (pinfunction "DQ8_D7") (pintype "bidirectional"))
    )
    (net (code "37") (name "/DDR-D9") (class "Default")
      (node (ref "U10") (pin "C3") (pinfunction "DQ9_C3") (pintype "bidirectional"))
    )
    (net (code "38") (name "/DDR-D10") (class "Default")
      (node (ref "U10") (pin "C8") (pinfunction "DQ10_C8") (pintype "bidirectional"))
    )
    (net (code "39") (name "/DDR-D11") (class "Default")
      (node (ref "U10") (pin "C2") (pinfunction "DQ11_C2") (pintype "bidirectional"))
    )
    (net (code "40") (name "/DDR-D12") (class "Default")
      (node (ref "U10") (pin "A7") (pinfunction "DQ12_A7") (pintype "bidirectional"))
    )
    (net (code "41") (name "/DDR-D13") (class "Default")
      (node (ref "U10") (pin "A2") (pinfunction "DQ13_A2") (pintype "bidirectional"))
    )
    (net (code "42") (name "/DDR-D14") (class "Default")
      (node (ref "U10") (pin "B8") (pinfunction "DQ14_B8") (pintype "bidirectional"))
    )
    (net (code "43") (name "/DDR-D15") (class "Default")
      (node (ref "U10") (pin "A3") (pinfunction "DQ15_A3") (pintype "bidirectional"))
    )
    (net (code "44") (name "/DDR-D16") (class "Default")
      (node (ref "U9") (pin "E3") (pinfunction "DQ0_E3") (pintype "bidirectional"))
    )
    (net (code "45") (name "/DDR-D17") (class "Default")
      (node (ref "U9") (pin "F7") (pinfunction "DQ1_F7") (pintype "bidirectional"))
    )
    (net (code "46") (name "/DDR-D18") (class "Default")
      (node (ref "U9") (pin "F2") (pinfunction "DQ2_F2") (pintype "bidirectional"))
    )
    (net (code "47") (name "/DDR-D19") (class "Default")
      (node (ref "U9") (pin "F8") (pinfunction "DQ3_F8") (pintype "bidirectional"))
    )
    (net (code "48") (name "/DDR-D20") (class "Default")
      (node (ref "U9") (pin "H3") (pinfunction "DQ4_H3") (pintype "bidirectional"))
    )
    (net (code "49") (name "/DDR-D21") (class "Default")
      (node (ref "U9") (pin "H8") (pinfunction "DQ5_H8") (pintype "bidirectional"))
    )
    (net (code "50") (name "/DDR-D22") (class "Default")
      (node (ref "U9") (pin "G2") (pinfunction "DQ6_G2") (pintype "bidirectional"))
    )
    (net (code "51") (name "/DDR-D23") (class "Default")
      (node (ref "U9") (pin "H7") (pinfunction "DQ7_H7") (pintype "bidirectional"))
    )
    (net (code "52") (name "/DDR-D24") (class "Default")
      (node (ref "U9") (pin "D7") (pinfunction "DQ8_D7") (pintype "bidirectional"))
    )
    (net (code "53") (name "/DDR-D25") (class "Default")
      (node (ref "U9") (pin "C3") (pinfunction "DQ9_C3") (pintype "bidirectional"))
    )
    (net (code "54") (name "/DDR-D26") (class "Default")
      (node (ref "U9") (pin "C8") (pinfunction "DQ10_C8") (pintype "bidirectional"))
    )
    (net (code "55") (name "/DDR-D27") (class "Default")
      (node (ref "U9") (pin "C2") (pinfunction "DQ11_C2") (pintype "bidirectional"))
    )
    (net (code "56") (name "/DDR-D28") (class "Default")
      (node (ref "U9") (pin "A7") (pinfunction "DQ12_A7") (pintype "bidirectional"))
    )
    (net (code "57") (name "/DDR-D29") (class "Default")
      (node (ref "U9") (pin "A2") (pinfunction "DQ13_A2") (pintype "bidirectional"))
    )
    (net (code "58") (name "/DDR-D30") (class "Default")
      (node (ref "U9") (pin "B8") (pinfunction "DQ14_B8") (pintype "bidirectional"))
    )
    (net (code "59") (name "/DDR-D31") (class "Default")
      (node (ref "U9") (pin "A3") (pinfunction "DQ15_A3") (pintype "bidirectional"))
    )
    (net (code "60") (name "/DDR-DQM0") (class "Default")
      (node (ref "U10") (pin "E7") (pinfunction "LDM_E7") (pintype "bidirectional"))
    )
    (net (code "61") (name "/DDR-DQM1") (class "Default")
      (node (ref "U10") (pin "D3") (pinfunction "UDM_D3") (pintype "input"))
    )
    (net (code "62") (name "/DDR-DQM2") (class "Default")
      (node (ref "U9") (pin "E7") (pinfunction "LDM_E7") (pintype "bidirectional"))
    )
    (net (code "63") (name "/DDR-DQM3") (class "Default")
      (node (ref "U9") (pin "D3") (pinfunction "UDM_D3") (pintype "input"))
    )
    (net (code "64") (name "/DDR-DQS0_N") (class "Default")
      (node (ref "U10") (pin "G3") (pinfunction "LDQSn_G3") (pintype "bidirectional"))
    )
    (net (code "65") (name "/DDR-DQS0_P") (class "Default")
      (node (ref "U10") (pin "F3") (pinfunction "LDQS_F3") (pintype "bidirectional+no_connect"))
    )
    (net (code "66") (name "/DDR-DQS1_N") (class "Default")
      (node (ref "U10") (pin "B7") (pinfunction "UDQSn_B7") (pintype "bidirectional"))
    )
    (net (code "67") (name "/DDR-DQS1_P") (class "Default")
      (node (ref "U10") (pin "C7") (pinfunction "UDQS_C7") (pintype "bidirectional"))
    )
    (net (code "68") (name "/DDR-DQS2_N") (class "Default")
      (node (ref "U9") (pin "G3") (pinfunction "LDQSn_G3") (pintype "bidirectional"))
    )
    (net (code "69") (name "/DDR-DQS2_P") (class "Default")
      (node (ref "U9") (pin "F3") (pinfunction "LDQS_F3") (pintype "bidirectional"))
    )
    (net (code "70") (name "/DDR-DQS3_N") (class "Default")
      (node (ref "U9") (pin "B7") (pinfunction "UDQSn_B7") (pintype "bidirectional"))
    )
    (net (code "71") (name "/DDR-DQS3_P") (class "Default")
      (node (ref "U9") (pin "C7") (pinfunction "UDQS_C7") (pintype "bidirectional"))
    )
    (net (code "74") (name "/DDR-ODT") (class "Default")
      (node (ref "R198") (pin "3") (pinfunction "3_3") (pintype "passive"))
      (node (ref "U10") (pin "K1") (pinfunction "ODT_K1") (pintype "input"))
      (node (ref "U9") (pin "K1") (pinfunction "ODT_K1") (pintype "input"))
    )
    (net (code "75") (name "/DDR-RASn") (class "Default")
      (node (ref "R198") (pin "2") (pinfunction "2_2") (pintype "passive"))
      (node (ref "U10") (pin "J3") (pinfunction "RASn_J3") (pintype "input"))
      (node (ref "U9") (pin "J3") (pinfunction "RASn_J3") (pintype "input"))
    )
    (net (code "76") (name "/DDR-RSTn") (class "Default")
      (node (ref "R31") (pin "2") (pinfunction "2_2") (pintype "passive"))
      (node (ref "U10") (pin "T2") (pinfunction "~{RESET}_T2") (pintype "input"))
      (node (ref "U9") (pin "T2") (pinfunction "~{RESET}_T2") (pintype "input"))
    )
    (net (code "77") (name "/DDR-WEn") (class "Default")
      (node (ref "R34") (pin "1") (pinfunction "1_1") (pintype "passive"))
      (node (ref "U10") (pin "L3") (pinfunction "WEn_L3") (pintype "input"))
      (node (ref "U9") (pin "L3") (pinfunction "WEn_L3") (pintype "input"))
    )
    (net (code "78") (name "/ZQL") (class "Default")
      (node (ref "R38") (pin "1") (pinfunction "1_1") (pintype "passive"))
      (node (ref "U10") (pin "L8") (pinfunction "ZQ_L8") (pintype "passive"))
    )
    (net (code "79") (name "/ZQU") (class "Default")
      (node (ref "R35") (pin "1") (pinfunction "1_1") (pintype "passive"))
      (node (ref "U9") (pin "L8") (pinfunction "ZQ_L8") (pintype "passive"))
    )
    (net (code "81") (name "DDRVREF") (class "Default")
      (node (ref "C127") (pin "2") (pinfunction "2_2") (pintype "passive"))
      (node (ref "C128") (pin "2") (pinfunction "2_2") (pintype "passive"))
      (node (ref "C148") (pin "2") (pinfunction "2_2") (pintype "passive"))
      (node (ref "C150") (pin "2") (pinfunction "2_2") (pintype "passive"))
      (node (ref "U10") (pin "H1") (pinfunction "VREF_DQ_H1") (pintype "passive"))
      (node (ref "U10") (pin "M8") (pinfunction "VREFC_CA_M8") (pintype "power_in"))
      (node (ref "U9") (pin "H1") (pinfunction "VREF_DQ_H1") (pintype "passive"))
      (node (ref "U9") (pin "M8") (pinfunction "VREFC_CA_M8") (pintype "power_in"))
    )
    (net (code "82") (name "GND") (class "Default")
      (node (ref "C114") (pin "1") (pinfunction "1_1") (pintype "passive"))
      (node (ref "C115") (pin "1") (pinfunction "1_1") (pintype "passive"))
      (node (ref "C116") (pin "1") (pinfunction "1_1") (pintype "passive"))
      (node (ref "C117") (pin "1") (pinfunction "1_1") (pintype "passive"))
      (node (ref "C118") (pin "1") (pinfunction "1_1") (pintype "passive"))
      (node (ref "C119") (pin "1") (pinfunction "1_1") (pintype "passive"))
      (node (ref "C120") (pin "1") (pinfunction "1_1") (pintype "passive"))
      (node (ref "C121") (pin "1") (pinfunction "1_1") (pintype "passive"))
      (node (ref "C122") (pin "1") (pinfunction "1_1") (pintype "passive"))
      (node (ref "C123") (pin "1") (pinfunction "1_1") (pintype "passive"))
      (node (ref "C124") (pin "1") (pinfunction "1_1") (pintype "passive"))
      (node (ref "C125") (pin "1") (pinfunction "1_1") (pintype "passive"))
      (node (ref "C126") (pin "1") (pinfunction "1_1") (pintype "passive"))
      (node (ref "C127") (pin "1") (pinfunction "1_1") (pintype "passive"))
      (node (ref "C128") (pin "1") (pinfunction "1_1") (pintype "passive"))
      (node (ref "C129") (pin "1") (pinfunction "1_1") (pintype "passive"))
      (node (ref "C130") (pin "1") (pinfunction "1_1") (pintype "passive"))
      (node (ref "C131") (pin "1") (pinfunction "1_1") (pintype "passive"))
      (node (ref "C132") (pin "1") (pinfunction "1_1") (pintype "passive"))
      (node (ref "C134") (pin "1") (pinfunction "1_1") (pintype "passive"))
      (node (ref "C135") (pin "1") (pinfunction "1_1") (pintype "passive"))
      (node (ref "C137") (pin "1") (pinfunction "1_1") (pintype "passive"))
      (node (ref "C138") (pin "1") (pinfunction "1_1") (pintype "passive"))
      (node (ref "C139") (pin "1") (pinfunction "1_1") (pintype "passive"))
      (node (ref "C140") (pin "1") (pinfunction "1_1") (pintype "passive"))
      (node (ref "C141") (pin "1") (pinfunction "1_1") (pintype "passive"))
      (node (ref "C142") (pin "1") (pinfunction "1_1") (pintype "passive"))
      (node (ref "C143") (pin "1") (pinfunction "1_1") (pintype "passive"))
      (node (ref "C144") (pin "1") (pinfunction "1_1") (pintype "passive"))
      (node (ref "C145") (pin "1") (pinfunction "1_1") (pintype "passive"))
      (node (ref "C146") (pin "1") (pinfunction "1_1") (pintype "passive"))
      (node (ref "C147") (pin "1") (pinfunction "1_1") (pintype "passive"))
      (node (ref "C148") (pin "1") (pinfunction "1_1") (pintype "passive"))
      (node (ref "C149") (pin "1") (pinfunction "1_1") (pintype "passive"))
      (node (ref "C150") (pin "1") (pinfunction "1_1") (pintype "passive"))
      (node (ref "C151") (pin "1") (pinfunction "1_1") (pintype "passive"))
      (node (ref "C152") (pin "1") (pinfunction "1_1") (pintype "passive"))
      (node (ref "C153") (pin "1") (pinfunction "1_1") (pintype "passive"))
      (node (ref "C155") (pin "1") (pinfunction "1_1") (pintype "passive"))
      (node (ref "C461") (pin "1") (pinfunction "1_1") (pintype "passive"))
      (node (ref "C462") (pin "1") (pinfunction "1_1") (pintype "passive"))
      (node (ref "C463") (pin "1") (pinfunction "1_1") (pintype "passive"))
      (node (ref "C464") (pin "1") (pinfunction "1_1") (pintype "passive"))
      (node (ref "C465") (pin "1") (pinfunction "1_1") (pintype "passive"))
      (node (ref "C466") (pin "1") (pinfunction "1_1") (pintype "passive"))
      (node (ref "C467") (pin "1") (pinfunction "1_1") (pintype "passive"))
      (node (ref "C468") (pin "1") (pinfunction "1_1") (pintype "passive"))
      (node (ref "C491") (pin "1") (pinfunction "1_1") (pintype "passive"))
      (node (ref "C492") (pin "1") (pinfunction "1_1") (pintype "passive"))
      (node (ref "R35") (pin "2") (pinfunction "2_2") (pintype "passive"))
      (node (ref "R38") (pin "2") (pinfunction "2_2") (pintype "passive"))
      (node (ref "U10") (pin "A9") (pinfunction "VSS_A9") (pintype "power_in"))
      (node (ref "U10") (pin "B1") (pinfunction "VSSQ_B1") (pintype "power_in"))
      (node (ref "U10") (pin "B3") (pinfunction "VSS_B3") (pintype "power_in"))
      (node (ref "U10") (pin "B9") (pinfunction "VSSQ_B9") (pintype "power_in"))
      (node (ref "U10") (pin "D1") (pinfunction "VSSQ_D1") (pintype "power_in"))
      (node (ref "U10") (pin "D8") (pinfunction "VSSQ_D8") (pintype "power_in"))
      (node (ref "U10") (pin "E1") (pinfunction "VSS_E1") (pintype "power_in"))
      (node (ref "U10") (pin "E2") (pinfunction "VSSQ_E2") (pintype "power_in"))
      (node (ref "U10") (pin "E8") (pinfunction "VSSQ_E8") (pintype "power_in"))
      (node (ref "U10") (pin "F9") (pinfunction "VSSQ_F9") (pintype "power_in"))
      (node (ref "U10") (pin "G1") (pinfunction "VSSQ_G1") (pintype "power_in"))
      (node (ref "U10") (pin "G8") (pinfunction "VSS_G8") (pintype "power_in"))
      (node (ref "U10") (pin "G9") (pinfunction "VSSQ_G9") (pintype "power_in"))
      (node (ref "U10") (pin "J2") (pinfunction "VSS_J2") (pintype "power_in"))
      (node (ref "U10") (pin "J8") (pinfunction "VSS_J8") (pintype "power_in"))
      (node (ref "U10") (pin "M1") (pinfunction "VSS_M1") (pintype "power_in"))
      (node (ref "U10") (pin "M9") (pinfunction "VSS_M9") (pintype "power_in"))
      (node (ref "U10") (pin "P1") (pinfunction "VSS_P1") (pintype "power_in"))
      (node (ref "U10") (pin "P9") (pinfunction "VSS_P9") (pintype "power_in"))
      (node (ref "U10") (pin "T1") (pinfunction "VSS_T1") (pintype "power_in"))
      (node (ref "U10") (pin "T9") (pinfunction "VSS_T9") (pintype "power_in"))
      (node (ref "U9") (pin "A9") (pinfunction "VSS_A9") (pintype "power_in"))
      (node (ref "U9") (pin "B1") (pinfunction "VSSQ_B1") (pintype "power_in"))
      (node (ref "U9") (pin "B3") (pinfunction "VSS_B3") (pintype "power_in"))
      (node (ref "U9") (pin "B9") (pinfunction "VSSQ_B9") (pintype "power_in"))
      (node (ref "U9") (pin "D1") (pinfunction "VSSQ_D1") (pintype "power_in"))
      (node (ref "U9") (pin "D8") (pinfunction "VSSQ_D8") (pintype "power_in"))
      (node (ref "U9") (pin "E1") (pinfunction "VSS_E1") (pintype "power_in"))
      (node (ref "U9") (pin "E2") (pinfunction "VSSQ_E2") (pintype "power_in"))
      (node (ref "U9") (pin "E8") (pinfunction "VSSQ_E8") (pintype "power_in"))
      (node (ref "U9") (pin "F9") (pinfunction "VSSQ_F9") (pintype "power_in"))
      (node (ref "U9") (pin "G1") (pinfunction "VSSQ_G1") (pintype "power_in"))
      (node (ref "U9") (pin "G8") (pinfunction "VSS_G8") (pintype "power_in"))
      (node (ref "U9") (pin "G9") (pinfunction "VSSQ_G9") (pintype "power_in"))
      (node (ref "U9") (pin "J2") (pinfunction "VSS_J2") (pintype "power_in"))
      (node (ref "U9") (pin "J8") (pinfunction "VSS_J8") (pintype "power_in"))
      (node (ref "U9") (pin "M1") (pinfunction "VSS_M1") (pintype "power_in"))
      (node (ref "U9") (pin "M9") (pinfunction "VSS_M9") (pintype "power_in"))
      (node (ref "U9") (pin "P1") (pinfunction "VSS_P1") (pintype "power_in"))
      (node (ref "U9") (pin "P9") (pinfunction "VSS_P9") (pintype "power_in"))
      (node (ref "U9") (pin "T1") (pinfunction "VSS_T1") (pintype "power_in"))
      (node (ref "U9") (pin "T9") (pinfunction "VSS_T9") (pintype "power_in"))
    )
    (net (code "83") (name "Net-(C114-Pad2)") (class "Default")
      (node (ref "C114") (pin "2") (pinfunction "2_2") (pintype "passive"))
      (node (ref "R29") (pin "7") (pinfunction "7_7") (pintype "passive"))
      (node (ref "R29") (pin "8") (pinfunction "8_8") (pintype "passive"))
    )
    (net (code "84") (name "PP0V68") (class "Default")
      (node (ref "C134") (pin "2") (pinfunction "2_2") (pintype "passive"))
      (node (ref "C137") (pin "2") (pinfunction "2_2") (pintype "passive"))
      (node (ref "C491") (pin "2") (pinfunction "2_2") (pintype "passive"))
      (node (ref "C492") (pin "2") (pinfunction "2_2") (pintype "passive"))
      (node (ref "R198") (pin "5") (pinfunction "5_5") (pintype "passive"))
      (node (ref "R198") (pin "6") (pinfunction "6_6") (pintype "passive"))
      (node (ref "R198") (pin "7") (pinfunction "7_7") (pintype "passive"))
      (node (ref "R198") (pin "8") (pinfunction "8_8") (pintype "passive"))
      (node (ref "R199") (pin "5") (pinfunction "5_5") (pintype "passive"))
      (node (ref "R199") (pin "6") (pinfunction "6_6") (pintype "passive"))
      (node (ref "R199") (pin "7") (pinfunction "7_7") (pintype "passive"))
      (node (ref "R199") (pin "8") (pinfunction "8_8") (pintype "passive"))
      (node (ref "R200") (pin "5") (pinfunction "5_5") (pintype "passive"))
      (node (ref "R200") (pin "6") (pinfunction "6_6") (pintype "passive"))
      (node (ref "R200") (pin "7") (pinfunction "7_7") (pintype "passive"))
      (node (ref "R200") (pin "8") (pinfunction "8_8") (pintype "passive"))
      (node (ref "R29") (pin "5") (pinfunction "5_5") (pintype "passive"))
      (node (ref "R29") (pin "6") (pinfunction "6_6") (pintype "passive"))
      (node (ref "R32") (pin "5") (pinfunction "5_5") (pintype "passive"))
      (node (ref "R32") (pin "6") (pinfunction "6_6") (pintype "passive"))
      (node (ref "R32") (pin "7") (pinfunction "7_7") (pintype "passive"))
      (node (ref "R32") (pin "8") (pinfunction "8_8") (pintype "passive"))
      (node (ref "R33") (pin "5") (pinfunction "5_5") (pintype "passive"))
      (node (ref "R33") (pin "6") (pinfunction "6_6") (pintype "passive"))
      (node (ref "R33") (pin "7") (pinfunction "7_7") (pintype "passive"))
      (node (ref "R33") (pin "8") (pinfunction "8_8") (pintype "passive"))
      (node (ref "R34") (pin "5") (pinfunction "5_5") (pintype "passive"))
      (node (ref "R34") (pin "6") (pinfunction "6_6") (pintype "passive"))
      (node (ref "R34") (pin "7") (pinfunction "7_7") (pintype "passive"))
      (node (ref "R34") (pin "8") (pinfunction "8_8") (pintype "passive"))
    )
    (net (code "85") (name "V1V35") (class "Default")
      (node (ref "C115") (pin "2") (pinfunction "2_2") (pintype "passive"))
      (node (ref "C116") (pin "2") (pinfunction "2_2") (pintype "passive"))
      (node (ref "C117") (pin "2") (pinfunction "2_2") (pintype "passive"))
      (node (ref "C118") (pin "2") (pinfunction "2_2") (pintype "passive"))
      (node (ref "C119") (pin "2") (pinfunction "2_2") (pintype "passive"))
      (node (ref "C120") (pin "2") (pinfunction "2_2") (pintype "passive"))
      (node (ref "C121") (pin "2") (pinfunction "2_2") (pintype "passive"))
      (node (ref "C122") (pin "2") (pinfunction "2_2") (pintype "passive"))
      (node (ref "C123") (pin "2") (pinfunction "2_2") (pintype "passive"))
      (node (ref "C124") (pin "2") (pinfunction "2_2") (pintype "passive"))
      (node (ref "C125") (pin "2") (pinfunction "2_2") (pintype "passive"))
      (node (ref "C126") (pin "2") (pinfunction "2_2") (pintype "passive"))
      (node (ref "C129") (pin "2") (pinfunction "2_2") (pintype "passive"))
      (node (ref "C130") (pin "2") (pinfunction "2_2") (pintype "passive"))
      (node (ref "C131") (pin "2") (pinfunction "2_2") (pintype "passive"))
      (node (ref "C132") (pin "2") (pinfunction "2_2") (pintype "passive"))
      (node (ref "C135") (pin "2") (pinfunction "2_2") (pintype "passive"))
      (node (ref "C138") (pin "2") (pinfunction "2_2") (pintype "passive"))
      (node (ref "C139") (pin "2") (pinfunction "2_2") (pintype "passive"))
      (node (ref "C140") (pin "2") (pinfunction "2_2") (pintype "passive"))
      (node (ref "C141") (pin "2") (pinfunction "2_2") (pintype "passive"))
      (node (ref "C142") (pin "2") (pinfunction "2_2") (pintype "passive"))
      (node (ref "C143") (pin "2") (pinfunction "2_2") (pintype "passive"))
      (node (ref "C144") (pin "2") (pinfunction "2_2") (pintype "passive"))
      (node (ref "C145") (pin "2") (pinfunction "2_2") (pintype "passive"))
      (node (ref "C146") (pin "2") (pinfunction "2_2") (pintype "passive"))
      (node (ref "C147") (pin "2") (pinfunction "2_2") (pintype "passive"))
      (node (ref "C149") (pin "2") (pinfunction "2_2") (pintype "passive"))
      (node (ref "C151") (pin "2") (pinfunction "2_2") (pintype "passive"))
      (node (ref "C152") (pin "2") (pinfunction "2_2") (pintype "passive"))
      (node (ref "C153") (pin "2") (pinfunction "2_2") (pintype "passive"))
      (node (ref "C155") (pin "2") (pinfunction "2_2") (pintype "passive"))
      (node (ref "C461") (pin "2") (pinfunction "2_2") (pintype "passive"))
      (node (ref "C462") (pin "2") (pinfunction "2_2") (pintype "passive"))
      (node (ref "C463") (pin "2") (pinfunction "2_2") (pintype "passive"))
      (node (ref "C464") (pin "2") (pinfunction "2_2") (pintype "passive"))
      (node (ref "C465") (pin "2") (pinfunction "2_2") (pintype "passive"))
      (node (ref "C466") (pin "2") (pinfunction "2_2") (pintype "passive"))
      (node (ref "C467") (pin "2") (pinfunction "2_2") (pintype "passive"))
      (node (ref "C468") (pin "2") (pinfunction "2_2") (pintype "passive"))
      (node (ref "R31") (pin "1") (pinfunction "1_1") (pintype "passive"))
      (node (ref "U10") (pin "A1") (pinfunction "VDDQ_A1") (pintype "power_in"))
      (node (ref "U10") (pin "A8") (pinfunction "VDDQ_A8") (pintype "power_in"))
      (node (ref "U10") (pin "B2") (pinfunction "VDD_B2") (pintype "power_in"))
      (node (ref "U10") (pin "C1") (pinfunction "VDDQ_C1") (pintype "power_in"))
      (node (ref "U10") (pin "C9") (pinfunction "VDDQ_C9") (pintype "power_in"))
      (node (ref "U10") (pin "D2") (pinfunction "VDDQ_D2") (pintype "power_in"))
      (node (ref "U10") (pin "D9") (pinfunction "VDD_D9") (pintype "power_in"))
      (node (ref "U10") (pin "E9") (pinfunction "VDDQ_E9") (pintype "power_in"))
      (node (ref "U10") (pin "F1") (pinfunction "VDDQ_F1") (pintype "power_in"))
      (node (ref "U10") (pin "G7") (pinfunction "VDD_G7") (pintype "power_in"))
      (node (ref "U10") (pin "H2") (pinfunction "VDDQ_H2") (pintype "power_in"))
      (node (ref "U10") (pin "H9") (pinfunction "VDDQ_H9") (pintype "power_in"))
      (node (ref "U10") (pin "K2") (pinfunction "VDD_K2") (pintype "power_in"))
      (node (ref "U10") (pin "K8") (pinfunction "VDD_K8") (pintype "power_in"))
      (node (ref "U10") (pin "N1") (pinfunction "VDD_N1") (pintype "power_in"))
      (node (ref "U10") (pin "N9") (pinfunction "VDD_N9") (pintype "power_in"))
      (node (ref "U10") (pin "R1") (pinfunction "VDD_R1") (pintype "power_in"))
      (node (ref "U10") (pin "R9") (pinfunction "VDD_R9") (pintype "power_in"))
      (node (ref "U9") (pin "A1") (pinfunction "VDDQ_A1") (pintype "power_in"))
      (node (ref "U9") (pin "A8") (pinfunction "VDDQ_A8") (pintype "power_in"))
      (node (ref "U9") (pin "B2") (pinfunction "VDD_B2") (pintype "power_in"))
      (node (ref "U9") (pin "C1") (pinfunction "VDDQ_C1") (pintype "power_in"))
      (node (ref "U9") (pin "C9") (pinfunction "VDDQ_C9") (pintype "power_in"))
      (node (ref "U9") (pin "D2") (pinfunction "VDDQ_D2") (pintype "power_in"))
      (node (ref "U9") (pin "D9") (pinfunction "VDD_D9") (pintype "power_in"))
      (node (ref "U9") (pin "E9") (pinfunction "VDDQ_E9") (pintype "power_in"))
      (node (ref "U9") (pin "F1") (pinfunction "VDDQ_F1") (pintype "power_in"))
      (node (ref "U9") (pin "G7") (pinfunction "VDD_G7") (pintype "power_in"))
      (node (ref "U9") (pin "H2") (pinfunction "VDDQ_H2") (pintype "power_in"))
      (node (ref "U9") (pin "H9") (pinfunction "VDDQ_H9") (pintype "power_in"))
      (node (ref "U9") (pin "K2") (pinfunction "VDD_K2") (pintype "power_in"))
      (node (ref "U9") (pin "K8") (pinfunction "VDD_K8") (pintype "power_in"))
      (node (ref "U9") (pin "N1") (pinfunction "VDD_N1") (pintype "power_in"))
      (node (ref "U9") (pin "N9") (pinfunction "VDD_N9") (pintype "power_in"))
      (node (ref "U9") (pin "R1") (pinfunction "VDD_R1") (pintype "power_in"))
      (node (ref "U9") (pin "R9") (pinfunction "VDD_R9") (pintype "power_in"))
    )
    (net (code "86") (name "unconnected-(R199-Pad4)") (class "Default")
      (node (ref "R199") (pin "4") (pinfunction "4_4") (pintype "passive"))
    )
    (net (code "87") (name "unconnected-(U9-NC-PadJ1)") (class "Default")
      (node (ref "U9") (pin "J1") (pinfunction "NC_J1") (pintype "passive+no_connect"))
    )
    (net (code "88") (name "unconnected-(U9-NC-PadJ9)") (class "Default")
      (node (ref "U9") (pin "J9") (pinfunction "NC_J9") (pintype "passive+no_connect"))
    )
    (net (code "89") (name "unconnected-(U9-NC-PadL1)") (class "Default")
      (node (ref "U9") (pin "L1") (pinfunction "NC_L1") (pintype "power_in+no_connect"))
    )
    (net (code "90") (name "unconnected-(U9-NC-PadL9)") (class "Default")
      (node (ref "U9") (pin "L9") (pinfunction "NC_L9") (pintype "power_in+no_connect"))
    )
    (net (code "91") (name "unconnected-(U10-NC-PadJ1)") (class "Default")
      (node (ref "U10") (pin "J1") (pinfunction "NC_J1") (pintype "passive+no_connect"))
    )
    (net (code "92") (name "unconnected-(U10-NC-PadJ9)") (class "Default")
      (node (ref "U10") (pin "J9") (pinfunction "NC_J9") (pintype "passive+no_connect"))
    )
    (net (code "93") (name "unconnected-(U10-NC-PadL1)") (class "Default")
      (node (ref "U10") (pin "L1") (pinfunction "NC_L1") (pintype "power_in+no_connect"))
    )
    (net (code "94") (name "unconnected-(U10-NC-PadL9)") (class "Default")
      (node (ref "U10") (pin "L9") (pinfunction "NC_L9") (pintype "power_in+no_connect"))
    )
  )
)
